# Sheet1.net
KiCad netlist of a schematic drawn in Altium Designer
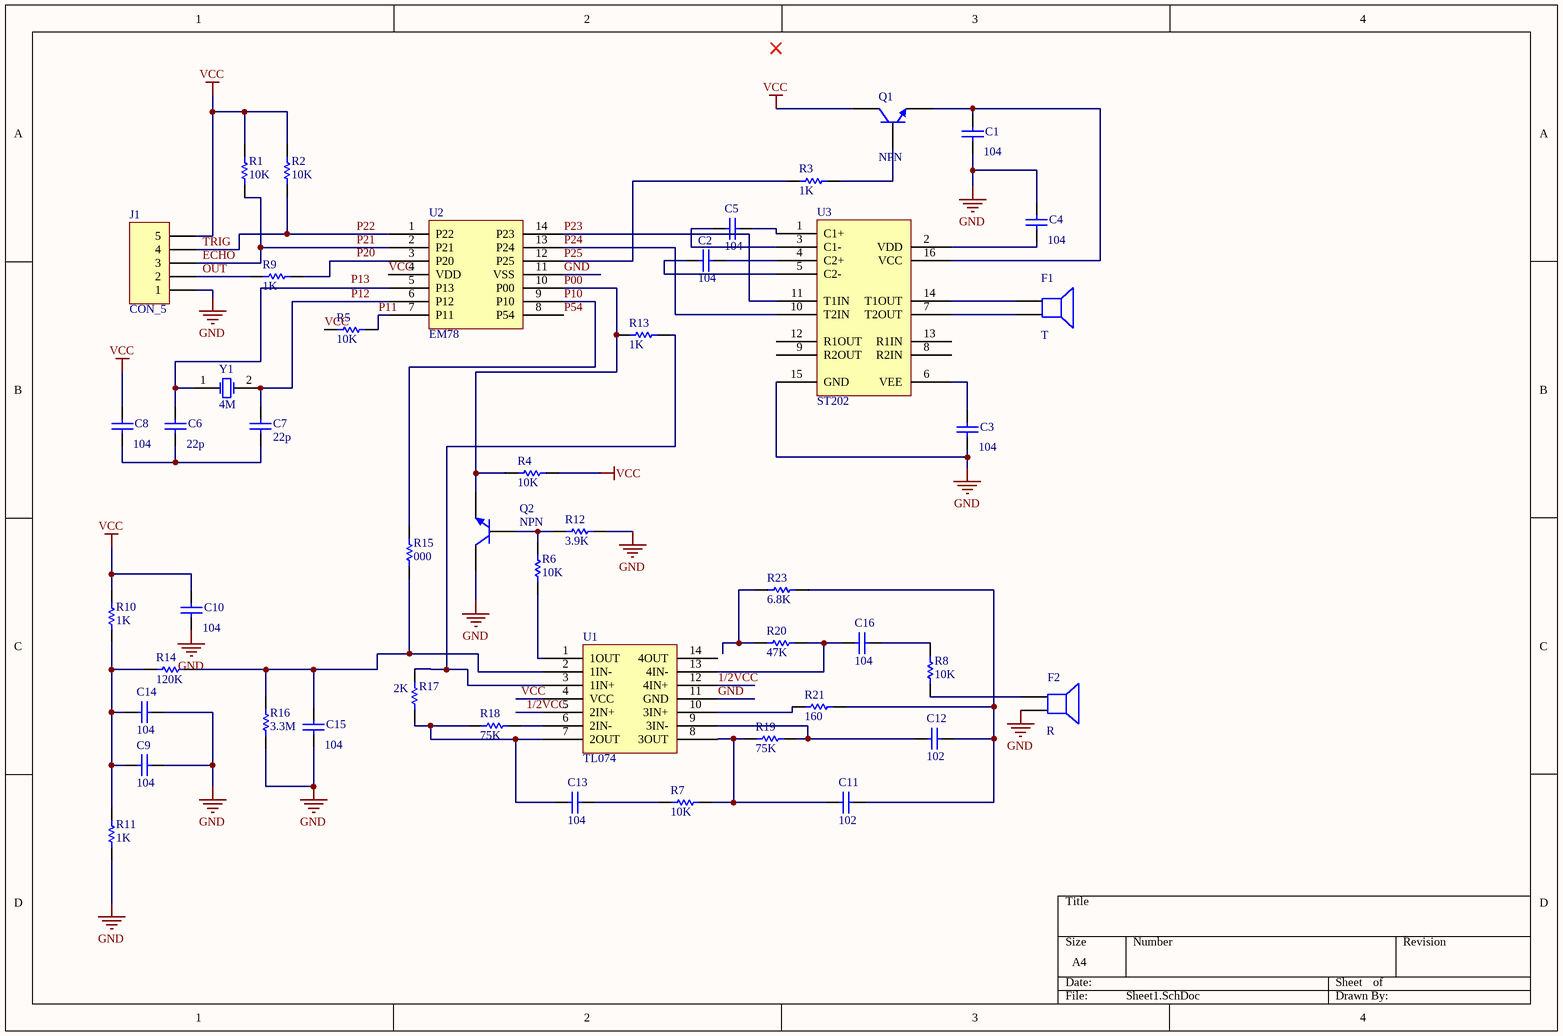
[diagram p0: Sheet1.SchDoc]

(export (version "E")
  (design (tool "Eeschema 10.0.6"))
  (components
    (comp (ref "C1")
      (value "104")
      (footprint "Miscellaneous Devices:1608[0603]")
      (description "Capacitor")
      (fields (field (name "Comment") "Cap") (field (name "PUBLISHER") "Altium Limited"))
      (libsource (lib "Miscellaneous Devices") (part "Cap"))
    )
    (comp (ref "C2")
      (value "104")
      (footprint "Miscellaneous Devices:1608[0603]")
      (description "Capacitor")
      (fields (field (name "Comment") "Cap") (field (name "PUBLISHER") "Altium Limited"))
      (libsource (lib "Miscellaneous Devices") (part "Cap"))
    )
    (comp (ref "C3")
      (value "104")
      (footprint "Miscellaneous Devices:1608[0603]")
      (description "Capacitor")
      (fields (field (name "Comment") "Cap") (field (name "PUBLISHER") "Altium Limited"))
      (libsource (lib "Miscellaneous Devices") (part "Cap"))
    )
    (comp (ref "C4")
      (value "104")
      (footprint "Miscellaneous Devices:1608[0603]")
      (description "Capacitor")
      (fields (field (name "Comment") "Cap") (field (name "PUBLISHER") "Altium Limited"))
      (libsource (lib "Miscellaneous Devices") (part "Cap"))
    )
    (comp (ref "C5")
      (value "104")
      (footprint "Miscellaneous Devices:1608[0603]")
      (description "Capacitor")
      (fields (field (name "Comment") "Cap") (field (name "PUBLISHER") "Altium Limited"))
      (libsource (lib "Miscellaneous Devices") (part "Cap"))
    )
    (comp (ref "C6")
      (value "22p")
      (footprint "Miscellaneous Devices:1608[0603]")
      (description "Capacitor")
      (fields (field (name "Comment") "Cap") (field (name "PUBLISHER") "Altium Limited"))
      (libsource (lib "Miscellaneous Devices") (part "Cap"))
    )
    (comp (ref "C7")
      (value "22p")
      (footprint "Miscellaneous Devices:1608[0603]")
      (description "Capacitor")
      (fields (field (name "Comment") "Cap") (field (name "PUBLISHER") "Altium Limited"))
      (libsource (lib "Miscellaneous Devices") (part "Cap"))
    )
    (comp (ref "C8")
      (value "104")
      (footprint "Miscellaneous Devices:1608[0603]")
      (description "Capacitor")
      (fields (field (name "Comment") "Cap") (field (name "PUBLISHER") "Altium Limited"))
      (libsource (lib "Miscellaneous Devices") (part "Cap"))
    )
    (comp (ref "C9")
      (value "104")
      (footprint "Miscellaneous Devices:1608[0603]")
      (description "Capacitor")
      (fields (field (name "Comment") "Cap") (field (name "PUBLISHER") "Altium Limited"))
      (libsource (lib "Miscellaneous Devices") (part "Cap"))
    )
    (comp (ref "C10")
      (value "104")
      (footprint "Miscellaneous Devices:1608[0603]")
      (description "Capacitor")
      (fields (field (name "Comment") "Cap") (field (name "PUBLISHER") "Altium Limited"))
      (libsource (lib "Miscellaneous Devices") (part "Cap"))
    )
    (comp (ref "C11")
      (value "102")
      (footprint "Miscellaneous Devices:1608[0603]")
      (description "Capacitor")
      (fields (field (name "Comment") "Cap") (field (name "PUBLISHER") "Altium Limited"))
      (libsource (lib "Miscellaneous Devices") (part "Cap"))
    )
    (comp (ref "C12")
      (value "102")
      (footprint "Miscellaneous Devices:1608[0603]")
      (description "Capacitor")
      (fields (field (name "Comment") "Cap") (field (name "PUBLISHER") "Altium Limited"))
      (libsource (lib "Miscellaneous Devices") (part "Cap"))
    )
    (comp (ref "C13")
      (value "104")
      (footprint "Miscellaneous Devices:1608[0603]")
      (description "Capacitor")
      (fields (field (name "Comment") "Cap") (field (name "PUBLISHER") "Altium Limited"))
      (libsource (lib "Miscellaneous Devices") (part "Cap"))
    )
    (comp (ref "C14")
      (value "104")
      (footprint "Miscellaneous Devices:1608[0603]")
      (description "Capacitor")
      (fields (field (name "Comment") "Cap") (field (name "PUBLISHER") "Altium Limited"))
      (libsource (lib "Miscellaneous Devices") (part "Cap"))
    )
    (comp (ref "C15")
      (value "104")
      (footprint "Miscellaneous Devices:1608[0603]")
      (description "Capacitor")
      (fields (field (name "Comment") "Cap") (field (name "PUBLISHER") "Altium Limited"))
      (libsource (lib "Miscellaneous Devices") (part "Cap"))
    )
    (comp (ref "C16")
      (value "104")
      (footprint "Miscellaneous Devices:1608[0603]")
      (description "Capacitor")
      (fields (field (name "Comment") "Cap") (field (name "PUBLISHER") "Altium Limited"))
      (libsource (lib "Miscellaneous Devices") (part "Cap"))
    )
    (comp (ref "F1")
      (value "T")
      (footprint "传感器fsc:laba")
      (description "Loudspeaker")
      (fields (field (name "PUBLISHER") "Altium Limited"))
      (libsource (lib "Miscellaneous Devices") (part "Speaker"))
    )
    (comp (ref "F2")
      (value "R")
      (footprint "传感器fsc:laba")
      (description "Loudspeaker")
      (fields (field (name "PUBLISHER") "Altium Limited"))
      (libsource (lib "Miscellaneous Devices") (part "Speaker"))
    )
    (comp (ref "J1")
      (value "CON_5")
      (footprint "HDR1X5")
      (description "Header, 5-Pin")
      (fields (field (name "PUBLISHER") "Altium Limited"))
      (libsource (lib "Miscellaneous Connectors") (part "Header 5"))
    )
    (comp (ref "Q1")
      (value "NPN")
      (footprint "Miscellaneous Devices:SOT-23_M")
      (description "NPN Bipolar Transistor")
      (fields (field (name "PUBLISHER") "Altium Limited"))
      (libsource (lib "Miscellaneous Devices") (part "NPN"))
    )
    (comp (ref "Q2")
      (value "NPN")
      (footprint "Miscellaneous Devices:SOT-23_M")
      (description "NPN Bipolar Transistor")
      (fields (field (name "PUBLISHER") "Altium Limited"))
      (libsource (lib "Miscellaneous Devices") (part "NPN"))
    )
    (comp (ref "R1")
      (value "10K")
      (footprint "Miscellaneous Devices:1608[0603]")
      (description "Resistor")
      (fields (field (name "Comment") "Res1") (field (name "PUBLISHER") "Altium Limited"))
      (libsource (lib "Miscellaneous Devices") (part "Res1"))
    )
    (comp (ref "R2")
      (value "10K")
      (footprint "Miscellaneous Devices:1608[0603]")
      (description "Resistor")
      (fields (field (name "Comment") "Res1") (field (name "PUBLISHER") "Altium Limited"))
      (libsource (lib "Miscellaneous Devices") (part "Res1"))
    )
    (comp (ref "R3")
      (value "1K")
      (footprint "Miscellaneous Devices:1608[0603]")
      (description "Resistor")
      (fields (field (name "Comment") "Res1") (field (name "PUBLISHER") "Altium Limited"))
      (libsource (lib "Miscellaneous Devices") (part "Res1"))
    )
    (comp (ref "R4")
      (value "10K")
      (footprint "Miscellaneous Devices:1608[0603]")
      (description "Resistor")
      (fields (field (name "Comment") "Res1") (field (name "PUBLISHER") "Altium Limited"))
      (libsource (lib "Miscellaneous Devices") (part "Res1"))
    )
    (comp (ref "R5")
      (value "10K")
      (footprint "Miscellaneous Devices:1608[0603]")
      (description "Resistor")
      (fields (field (name "Comment") "Res1") (field (name "PUBLISHER") "Altium Limited"))
      (libsource (lib "Miscellaneous Devices") (part "Res1"))
    )
    (comp (ref "R6")
      (value "10K")
      (footprint "Miscellaneous Devices:1608[0603]")
      (description "Resistor")
      (fields (field (name "Comment") "Res1") (field (name "PUBLISHER") "Altium Limited"))
      (libsource (lib "Miscellaneous Devices") (part "Res1"))
    )
    (comp (ref "R7")
      (value "10K")
      (footprint "Miscellaneous Devices:1608[0603]")
      (description "Resistor")
      (fields (field (name "Comment") "Res1") (field (name "PUBLISHER") "Altium Limited"))
      (libsource (lib "Miscellaneous Devices") (part "Res1"))
    )
    (comp (ref "R8")
      (value "10K")
      (footprint "Miscellaneous Devices:1608[0603]")
      (description "Resistor")
      (fields (field (name "Comment") "Res1") (field (name "PUBLISHER") "Altium Limited"))
      (libsource (lib "Miscellaneous Devices") (part "Res1"))
    )
    (comp (ref "R9")
      (value "1K")
      (footprint "Miscellaneous Devices:1608[0603]")
      (description "Resistor")
      (fields (field (name "Comment") "Res1") (field (name "PUBLISHER") "Altium Limited"))
      (libsource (lib "Miscellaneous Devices") (part "Res1"))
    )
    (comp (ref "R10")
      (value "1K")
      (footprint "Miscellaneous Devices:1608[0603]")
      (description "Resistor")
      (fields (field (name "Comment") "Res1") (field (name "PUBLISHER") "Altium Limited"))
      (libsource (lib "Miscellaneous Devices") (part "Res1"))
    )
    (comp (ref "R11")
      (value "1K")
      (footprint "Miscellaneous Devices:1608[0603]")
      (description "Resistor")
      (fields (field (name "Comment") "Res1") (field (name "PUBLISHER") "Altium Limited"))
      (libsource (lib "Miscellaneous Devices") (part "Res1"))
    )
    (comp (ref "R12")
      (value "3.9K")
      (footprint "Miscellaneous Devices:1608[0603]")
      (description "Resistor")
      (fields (field (name "Comment") "Res1") (field (name "PUBLISHER") "Altium Limited"))
      (libsource (lib "Miscellaneous Devices") (part "Res1"))
    )
    (comp (ref "R13")
      (value "1K")
      (footprint "Miscellaneous Devices:1608[0603]")
      (description "Resistor")
      (fields (field (name "Comment") "Res1") (field (name "PUBLISHER") "Altium Limited"))
      (libsource (lib "Miscellaneous Devices") (part "Res1"))
    )
    (comp (ref "R14")
      (value "120K")
      (footprint "Miscellaneous Devices:1608[0603]")
      (description "Resistor")
      (fields (field (name "Comment") "Res1") (field (name "PUBLISHER") "Altium Limited"))
      (libsource (lib "Miscellaneous Devices") (part "Res1"))
    )
    (comp (ref "R15")
      (value "000")
      (footprint "Miscellaneous Devices:1608[0603]")
      (description "Resistor")
      (fields (field (name "Comment") "Res1") (field (name "PUBLISHER") "Altium Limited"))
      (libsource (lib "Miscellaneous Devices") (part "Res1"))
    )
    (comp (ref "R16")
      (value "3.3M")
      (footprint "Miscellaneous Devices:1608[0603]")
      (description "Resistor")
      (fields (field (name "Comment") "Res1") (field (name "PUBLISHER") "Altium Limited"))
      (libsource (lib "Miscellaneous Devices") (part "Res1"))
    )
    (comp (ref "R17")
      (value "2K")
      (footprint "Miscellaneous Devices:1608[0603]")
      (description "Resistor")
      (fields (field (name "Comment") "Res1") (field (name "PUBLISHER") "Altium Limited"))
      (libsource (lib "Miscellaneous Devices") (part "Res1"))
    )
    (comp (ref "R18")
      (value "75K")
      (footprint "Miscellaneous Devices:1608[0603]")
      (description "Resistor")
      (fields (field (name "Comment") "Res1") (field (name "PUBLISHER") "Altium Limited"))
      (libsource (lib "Miscellaneous Devices") (part "Res1"))
    )
    (comp (ref "R19")
      (value "75K")
      (footprint "Miscellaneous Devices:1608[0603]")
      (description "Resistor")
      (fields (field (name "Comment") "Res1") (field (name "PUBLISHER") "Altium Limited"))
      (libsource (lib "Miscellaneous Devices") (part "Res1"))
    )
    (comp (ref "R20")
      (value "47K")
      (footprint "Miscellaneous Devices:1608[0603]")
      (description "Resistor")
      (fields (field (name "Comment") "Res1") (field (name "PUBLISHER") "Altium Limited"))
      (libsource (lib "Miscellaneous Devices") (part "Res1"))
    )
    (comp (ref "R21")
      (value "160")
      (footprint "Miscellaneous Devices:1608[0603]")
      (description "Resistor")
      (fields (field (name "Comment") "Res1") (field (name "PUBLISHER") "Altium Limited"))
      (libsource (lib "Miscellaneous Devices") (part "Res1"))
    )
    (comp (ref "R23")
      (value "6.8K")
      (footprint "Miscellaneous Devices:1608[0603]")
      (description "Resistor")
      (fields (field (name "Comment") "Res1") (field (name "PUBLISHER") "Altium Limited"))
      (libsource (lib "Miscellaneous Devices") (part "Res1"))
    )
    (comp (ref "U1") (value "TL074") (footprint "传感器fsc:SO_14") (libsource (lib "Schlib1") (part "TL074")))
    (comp (ref "U2") (value "EM78") (footprint "传感器fsc:SO_14") (libsource (lib "Schlib1") (part "EM78")))
    (comp (ref "U3")
      (value "ST202")
      (footprint "Miscellaneous Devices:SO-16_L")
      (libsource (lib "Schlib1") (part "ST202"))
    )
    (comp (ref "Y1")
      (value "4M")
      (footprint "传感器fsc:jingzhen")
      (description "Crystal Oscillator")
      (fields (field (name "PUBLISHER") "Altium Limited"))
      (libsource (lib "Miscellaneous Devices") (part "XTAL"))
    )
  )
  (nets
    (net (code "1") (name "/1{slash}2VCC") (class "Default")
      (node (ref "U1") (pin "12") (pinfunction "4IN+_12") (pintype "passive"))
      (node (ref "U1") (pin "5") (pinfunction "2IN+_5") (pintype "passive"))
    )
    (net (code "2") (name "/ECHO") (class "Default")
      (node (ref "J1") (pin "3") (pinfunction "3_3") (pintype "passive"))
      (node (ref "R1") (pin "1") (pinfunction "1_1") (pintype "passive"))
      (node (ref "U2") (pin "2") (pinfunction "P21_2") (pintype "passive"))
    )
    (net (code "3") (name "/OUT") (class "Default")
      (node (ref "J1") (pin "2") (pinfunction "2_2") (pintype "passive"))
      (node (ref "R9") (pin "2") (pinfunction "2_2") (pintype "passive"))
    )
    (net (code "4") (name "/P00") (class "Default")
      (node (ref "Q2") (pin "3") (pinfunction "E_3") (pintype "passive"))
      (node (ref "R13") (pin "2") (pinfunction "2_2") (pintype "passive"))
      (node (ref "R4") (pin "1") (pinfunction "1_1") (pintype "passive"))
      (node (ref "U2") (pin "10") (pinfunction "P00_10") (pintype "passive"))
    )
    (net (code "5") (name "/P10") (class "Default")
      (node (ref "R15") (pin "1") (pinfunction "1_1") (pintype "passive"))
      (node (ref "U2") (pin "9") (pinfunction "P10_9") (pintype "passive"))
    )
    (net (code "6") (name "/P11") (class "Default")
      (node (ref "R5") (pin "1") (pinfunction "1_1") (pintype "passive"))
      (node (ref "U2") (pin "7") (pinfunction "P11_7") (pintype "passive"))
    )
    (net (code "7") (name "/P12") (class "Default")
      (node (ref "C7") (pin "1") (pinfunction "1_1") (pintype "passive"))
      (node (ref "U2") (pin "6") (pinfunction "P12_6") (pintype "passive"))
      (node (ref "Y1") (pin "2") (pinfunction "OSC2_2") (pintype "passive"))
    )
    (net (code "10") (name "/P20") (class "Default")
      (node (ref "R9") (pin "1") (pinfunction "1_1") (pintype "passive"))
      (node (ref "U2") (pin "3") (pinfunction "P20_3") (pintype "passive"))
    )
    (net (code "11") (name "/P22") (class "Default")
      (node (ref "J1") (pin "4") (pinfunction "4_4") (pintype "passive"))
      (node (ref "R2") (pin "1") (pinfunction "1_1") (pintype "passive"))
      (node (ref "U2") (pin "1") (pinfunction "P22_1") (pintype "passive"))
    )
    (net (code "12") (name "/P23") (class "Default")
      (node (ref "U2") (pin "14") (pinfunction "P23_14") (pintype "passive"))
      (node (ref "U3") (pin "11") (pinfunction "T1IN_11") (pintype "passive"))
    )
    (net (code "13") (name "/P24") (class "Default")
      (node (ref "U2") (pin "13") (pinfunction "P24_13") (pintype "passive"))
      (node (ref "U3") (pin "10") (pinfunction "T2IN_10") (pintype "passive"))
    )
    (net (code "14") (name "/P25") (class "Default")
      (node (ref "R3") (pin "2") (pinfunction "2_2") (pintype "passive"))
      (node (ref "U2") (pin "12") (pinfunction "P25_12") (pintype "passive"))
    )
    (net (code "15") (name "/P54") (class "Default")
      (node (ref "U2") (pin "8") (pinfunction "P54_8") (pintype "passive"))
    )
    (net (code "16") (name "GND") (class "Default")
      (node (ref "C1") (pin "1") (pinfunction "1_1") (pintype "passive"))
      (node (ref "C10") (pin "1") (pinfunction "1_1") (pintype "passive"))
      (node (ref "C14") (pin "1") (pinfunction "1_1") (pintype "passive"))
      (node (ref "C15") (pin "1") (pinfunction "1_1") (pintype "passive"))
      (node (ref "C3") (pin "1") (pinfunction "1_1") (pintype "passive"))
      (node (ref "C4") (pin "2") (pinfunction "2_2") (pintype "passive"))
      (node (ref "C9") (pin "1") (pinfunction "1_1") (pintype "passive"))
      (node (ref "F2") (pin "2") (pinfunction "2_2") (pintype "passive"))
      (node (ref "J1") (pin "1") (pinfunction "1_1") (pintype "passive"))
      (node (ref "Q2") (pin "1") (pinfunction "C_1") (pintype "passive"))
      (node (ref "R11") (pin "2") (pinfunction "2_2") (pintype "passive"))
      (node (ref "R12") (pin "2") (pinfunction "2_2") (pintype "passive"))
      (node (ref "R16") (pin "2") (pinfunction "2_2") (pintype "passive"))
      (node (ref "U1") (pin "11") (pinfunction "GND_11") (pintype "passive"))
      (node (ref "U2") (pin "11") (pinfunction "VSS_11") (pintype "passive"))
      (node (ref "U3") (pin "15") (pinfunction "GND_15") (pintype "passive"))
    )
    (net (code "17") (name "Net-(C6-Pad1)") (class "Default")
      (node (ref "C6") (pin "1") (pinfunction "1_1") (pintype "passive"))
      (node (ref "C7") (pin "2") (pinfunction "2_2") (pintype "passive"))
      (node (ref "C8") (pin "1") (pinfunction "1_1") (pintype "passive"))
    )
    (net (code "18") (name "Net-(C11-Pad1)") (class "Default")
      (node (ref "C11") (pin "1") (pinfunction "1_1") (pintype "passive"))
      (node (ref "C12") (pin "1") (pinfunction "1_1") (pintype "passive"))
      (node (ref "R21") (pin "1") (pinfunction "1_1") (pintype "passive"))
      (node (ref "R23") (pin "2") (pinfunction "2_2") (pintype "passive"))
    )
    (net (code "19") (name "Net-(C13-Pad1)") (class "Default")
      (node (ref "C13") (pin "1") (pinfunction "1_1") (pintype "passive"))
      (node (ref "R7") (pin "1") (pinfunction "1_1") (pintype "passive"))
    )
    (net (code "20") (name "Net-(C14-Pad2)") (class "Default")
      (node (ref "C14") (pin "2") (pinfunction "2_2") (pintype "passive"))
      (node (ref "C9") (pin "2") (pinfunction "2_2") (pintype "passive"))
      (node (ref "R10") (pin "2") (pinfunction "2_2") (pintype "passive"))
      (node (ref "R11") (pin "1") (pinfunction "1_1") (pintype "passive"))
      (node (ref "R14") (pin "1") (pinfunction "1_1") (pintype "passive"))
    )
    (net (code "21") (name "Net-(C16-Pad1)") (class "Default")
      (node (ref "C16") (pin "1") (pinfunction "1_1") (pintype "passive"))
      (node (ref "R8") (pin "2") (pinfunction "2_2") (pintype "passive"))
    )
    (net (code "22") (name "Net-(F2-Pad1)") (class "Default")
      (node (ref "F2") (pin "1") (pinfunction "1_1") (pintype "passive"))
      (node (ref "R8") (pin "1") (pinfunction "1_1") (pintype "passive"))
    )
    (net (code "23") (name "Net-(Q1-B)") (class "Default")
      (node (ref "Q1") (pin "2") (pinfunction "B_2") (pintype "passive"))
      (node (ref "R3") (pin "1") (pinfunction "1_1") (pintype "passive"))
    )
    (net (code "24") (name "Net-(Q1-E)") (class "Default")
      (node (ref "C1") (pin "2") (pinfunction "2_2") (pintype "passive"))
      (node (ref "Q1") (pin "3") (pinfunction "E_3") (pintype "passive"))
      (node (ref "U3") (pin "16") (pinfunction "VCC_16") (pintype "passive"))
    )
    (net (code "25") (name "Net-(Q2-B)") (class "Default")
      (node (ref "Q2") (pin "2") (pinfunction "B_2") (pintype "passive"))
      (node (ref "R12") (pin "1") (pinfunction "1_1") (pintype "passive"))
      (node (ref "R6") (pin "1") (pinfunction "1_1") (pintype "passive"))
    )
    (net (code "26") (name "Net-(R20-Pad1)") (class "Default")
      (node (ref "R20") (pin "1") (pinfunction "1_1") (pintype "passive"))
      (node (ref "R23") (pin "1") (pinfunction "1_1") (pintype "passive"))
    )
    (net (code "27") (name "Net-(U1-1IN+)") (class "Default")
      (node (ref "R13") (pin "1") (pinfunction "1_1") (pintype "passive"))
      (node (ref "R17") (pin "1") (pinfunction "1_1") (pintype "passive"))
      (node (ref "U1") (pin "3") (pinfunction "1IN+_3") (pintype "passive"))
    )
    (net (code "28") (name "Net-(U1-1IN-)") (class "Default")
      (node (ref "C15") (pin "2") (pinfunction "2_2") (pintype "passive"))
      (node (ref "R14") (pin "2") (pinfunction "2_2") (pintype "passive"))
      (node (ref "R15") (pin "2") (pinfunction "2_2") (pintype "passive"))
      (node (ref "R16") (pin "1") (pinfunction "1_1") (pintype "passive"))
      (node (ref "U1") (pin "2") (pinfunction "1IN-_2") (pintype "passive"))
    )
    (net (code "29") (name "Net-(U1-1OUT)") (class "Default")
      (node (ref "R6") (pin "2") (pinfunction "2_2") (pintype "passive"))
      (node (ref "U1") (pin "1") (pinfunction "1OUT_1") (pintype "passive"))
    )
    (net (code "30") (name "Net-(U1-2IN-)") (class "Default")
      (node (ref "R18") (pin "2") (pinfunction "2_2") (pintype "passive"))
      (node (ref "U1") (pin "6") (pinfunction "2IN-_6") (pintype "passive"))
    )
    (net (code "31") (name "Net-(U1-2OUT)") (class "Default")
      (node (ref "C13") (pin "2") (pinfunction "2_2") (pintype "passive"))
      (node (ref "R17") (pin "2") (pinfunction "2_2") (pintype "passive"))
      (node (ref "R18") (pin "1") (pinfunction "1_1") (pintype "passive"))
      (node (ref "U1") (pin "7") (pinfunction "2OUT_7") (pintype "passive"))
    )
    (net (code "32") (name "Net-(U1-3IN+)") (class "Default")
      (node (ref "R21") (pin "2") (pinfunction "2_2") (pintype "passive"))
      (node (ref "U1") (pin "10") (pinfunction "3IN+_10") (pintype "passive"))
    )
    (net (code "33") (name "Net-(U1-3IN-)") (class "Default")
      (node (ref "C12") (pin "2") (pinfunction "2_2") (pintype "passive"))
      (node (ref "R19") (pin "2") (pinfunction "2_2") (pintype "passive"))
      (node (ref "U1") (pin "9") (pinfunction "3IN-_9") (pintype "passive"))
    )
    (net (code "34") (name "Net-(U1-3OUT)") (class "Default")
      (node (ref "C11") (pin "2") (pinfunction "2_2") (pintype "passive"))
      (node (ref "R19") (pin "1") (pinfunction "1_1") (pintype "passive"))
      (node (ref "R7") (pin "2") (pinfunction "2_2") (pintype "passive"))
      (node (ref "U1") (pin "8") (pinfunction "3OUT_8") (pintype "passive"))
    )
    (net (code "35") (name "Net-(U1-4IN-)") (class "Default")
      (node (ref "C16") (pin "2") (pinfunction "2_2") (pintype "passive"))
      (node (ref "R20") (pin "2") (pinfunction "2_2") (pintype "passive"))
      (node (ref "U1") (pin "13") (pinfunction "4IN-_13") (pintype "passive"))
    )
    (net (code "36") (name "Net-(U2-P13)") (class "Default")
      (node (ref "C6") (pin "2") (pinfunction "2_2") (pintype "passive"))
      (node (ref "U2") (pin "5") (pinfunction "P13_5") (pintype "passive"))
      (node (ref "Y1") (pin "1") (pinfunction "OSC1_1") (pintype "passive"))
    )
    (net (code "37") (name "Net-(U3-C1+)") (class "Default")
      (node (ref "C5") (pin "1") (pinfunction "1_1") (pintype "passive"))
      (node (ref "U3") (pin "1") (pinfunction "C1+_1") (pintype "passive"))
    )
    (net (code "38") (name "Net-(U3-C1-)") (class "Default")
      (node (ref "C5") (pin "2") (pinfunction "2_2") (pintype "passive"))
      (node (ref "U3") (pin "3") (pinfunction "C1-_3") (pintype "passive"))
    )
    (net (code "39") (name "Net-(U3-C2+)") (class "Default")
      (node (ref "C2") (pin "1") (pinfunction "1_1") (pintype "passive"))
      (node (ref "U3") (pin "4") (pinfunction "C2+_4") (pintype "passive"))
    )
    (net (code "40") (name "Net-(U3-C2-)") (class "Default")
      (node (ref "C2") (pin "2") (pinfunction "2_2") (pintype "passive"))
      (node (ref "U3") (pin "5") (pinfunction "C2-_5") (pintype "passive"))
    )
    (net (code "41") (name "Net-(U3-T1OUT)") (class "Default")
      (node (ref "F1") (pin "1") (pinfunction "1_1") (pintype "passive"))
      (node (ref "U3") (pin "14") (pinfunction "T1OUT_14") (pintype "passive"))
    )
    (net (code "42") (name "Net-(U3-T2OUT)") (class "Default")
      (node (ref "F1") (pin "2") (pinfunction "2_2") (pintype "passive"))
      (node (ref "U3") (pin "7") (pinfunction "T2OUT_7") (pintype "passive"))
    )
    (net (code "43") (name "Net-(U3-VDD)") (class "Default")
      (node (ref "C4") (pin "1") (pinfunction "1_1") (pintype "passive"))
      (node (ref "U3") (pin "2") (pinfunction "VDD_2") (pintype "passive"))
    )
    (net (code "44") (name "Net-(U3-VEE)") (class "Default")
      (node (ref "C3") (pin "2") (pinfunction "2_2") (pintype "passive"))
      (node (ref "U3") (pin "6") (pinfunction "VEE_6") (pintype "passive"))
    )
    (net (code "45") (name "VCC") (class "Default")
      (node (ref "C10") (pin "2") (pinfunction "2_2") (pintype "passive"))
      (node (ref "C8") (pin "2") (pinfunction "2_2") (pintype "passive"))
      (node (ref "J1") (pin "5") (pinfunction "5_5") (pintype "passive"))
      (node (ref "Q1") (pin "1") (pinfunction "C_1") (pintype "passive"))
      (node (ref "R1") (pin "2") (pinfunction "2_2") (pintype "passive"))
      (node (ref "R10") (pin "1") (pinfunction "1_1") (pintype "passive"))
      (node (ref "R2") (pin "2") (pinfunction "2_2") (pintype "passive"))
      (node (ref "R4") (pin "2") (pinfunction "2_2") (pintype "passive"))
      (node (ref "R5") (pin "2") (pinfunction "2_2") (pintype "passive"))
      (node (ref "U1") (pin "4") (pinfunction "VCC_4") (pintype "passive"))
      (node (ref "U2") (pin "4") (pinfunction "VDD_4") (pintype "passive"))
    )
    (net (code "46") (name "unconnected-(U1-4OUT-Pad14)") (class "Default")
      (node (ref "U1") (pin "14") (pinfunction "4OUT_14") (pintype "passive"))
    )
    (net (code "47") (name "unconnected-(U3-R1IN-Pad13)") (class "Default")
      (node (ref "U3") (pin "13") (pinfunction "R1IN_13") (pintype "passive"))
    )
    (net (code "48") (name "unconnected-(U3-R1OUT-Pad12)") (class "Default")
      (node (ref "U3") (pin "12") (pinfunction "R1OUT_12") (pintype "passive"))
    )
    (net (code "49") (name "unconnected-(U3-R2IN-Pad8)") (class "Default")
      (node (ref "U3") (pin "8") (pinfunction "R2IN_8") (pintype "passive"))
    )
    (net (code "50") (name "unconnected-(U3-R2OUT-Pad9)") (class "Default")
      (node (ref "U3") (pin "9") (pinfunction "R2OUT_9") (pintype "passive"))
    )
  )
)
